# Antenna.net
KiCad netlist of a schematic drawn in Altium Designer
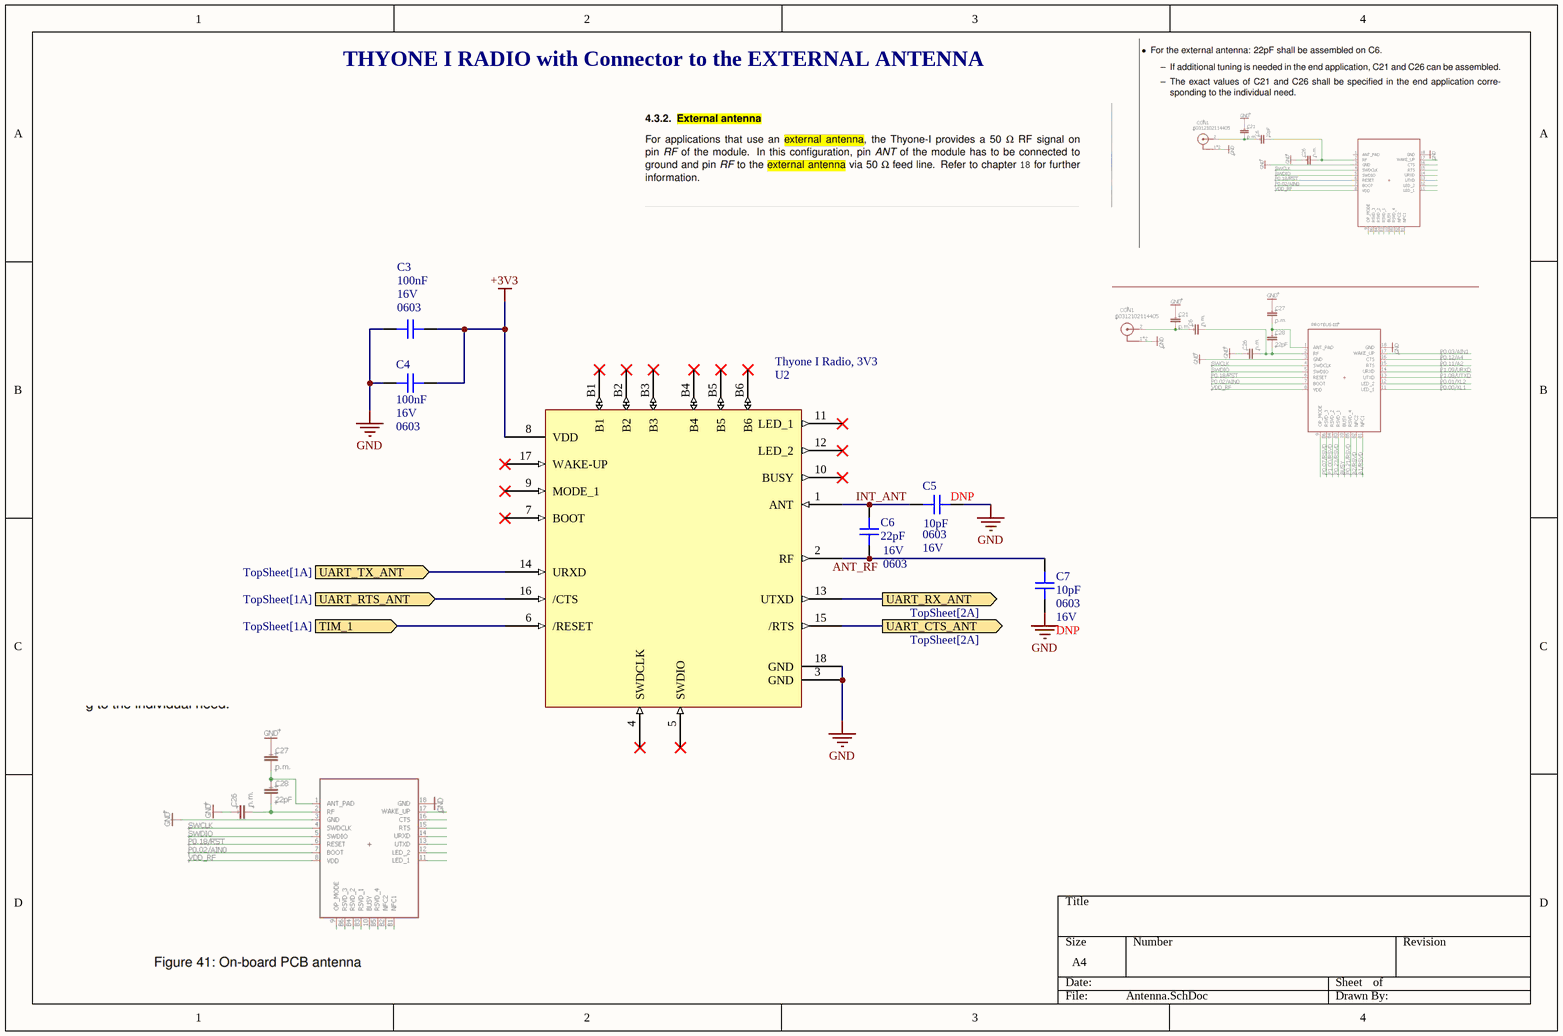
[diagram p0: Antenna.SchDoc]

(export (version "E")
  (design (tool "Eeschema 10.0.6"))
  (components
    (comp (ref "C3")
      (value "100nF")
      (footprint "0603_C")
      (description "CAP CER 0.1UF 16V X7R 0603")
      (fields
        (field (name "VOLTAGE - RATED") "16V")
        (field (name "TOLERANCE") "10%")
        (field (name "PACKAGE / CASE") "0603")
        (field (name "MANUFACTURE PART NUMBER") "KGM15AR71C104KM")
      )
      (libsource (lib "Aleksandra Popova") (part "Capacitor - Non Polarized"))
    )
    (comp (ref "C4")
      (value "100nF")
      (footprint "0603_C")
      (description "CAP CER 0.1UF 16V X7R 0603")
      (fields
        (field (name "VOLTAGE - RATED") "16V")
        (field (name "TOLERANCE") "10%")
        (field (name "PACKAGE / CASE") "0603")
        (field (name "MANUFACTURE PART NUMBER") "KGM15AR71C104KM")
      )
      (libsource (lib "Aleksandra Popova") (part "Capacitor - Non Polarized"))
    )
    (comp (ref "C5")
      (value "DNP")
      (footprint "0603_C")
      (description "CAP CER 10PF 16V C0G/NP0 0603")
      (fields
        (field (name "TOLERANCE") "5%")
        (field (name "MANUFACTURE PART NUMBER") "KGM15ACG1C100JT")
        (field (name "ALTIUM_VALUE") "10pF")
        (field (name "PACKAGE / CASE") "0603")
        (field (name "VOLTAGE - RATED") "16V")
      )
      (libsource (lib "Aleksandra Popova") (part "Capacitor - Non Polarized"))
    )
    (comp (ref "C6")
      (value "22pF")
      (footprint "0603_C")
      (description "CAP CER 22PF 16V C0G/NP0 0603")
      (fields
        (field (name "VOLTAGE - RATED") "16V")
        (field (name "TOLERANCE") "10%")
        (field (name "PACKAGE / CASE") "0603")
        (field (name "MANUFACTURE PART NUMBER") "KGM15ACG1C220KT")
      )
      (libsource (lib "Aleksandra Popova") (part "Capacitor - Non Polarized"))
    )
    (comp (ref "C7")
      (value "DNP")
      (footprint "0603_C")
      (description "CAP CER 10PF 16V C0G/NP0 0603")
      (fields
        (field (name "TOLERANCE") "5%")
        (field (name "MANUFACTURE PART NUMBER") "KGM15ACG1C100JT")
        (field (name "ALTIUM_VALUE") "10pF")
        (field (name "PACKAGE / CASE") "0603")
        (field (name "VOLTAGE - RATED") "16V")
      )
      (libsource (lib "Aleksandra Popova") (part "Capacitor - Non Polarized"))
    )
    (comp (ref "U2")
      (value "Thyone I Radio, 3V3")
      (footprint "WE-FP-4+")
      (libsource (lib "Schlib1") (part "2611011021000"))
    )
  )
  (nets
    (net (code "1") (name "+3V3") (class "Default")
      (node (ref "C3") (pin "2") (pinfunction "2_2") (pintype "passive"))
      (node (ref "C4") (pin "1") (pinfunction "1_1") (pintype "passive"))
      (node (ref "U2") (pin "8") (pinfunction "VDD_8") (pintype "passive"))
    )
    (net (code "2") (name "/ANT_RF") (class "Default")
      (node (ref "C6") (pin "1") (pinfunction "1_1") (pintype "passive"))
      (node (ref "C7") (pin "1") (pinfunction "1_1") (pintype "passive"))
      (node (ref "U2") (pin "2") (pinfunction "RF_2") (pintype "output"))
    )
    (net (code "3") (name "/INT_ANT") (class "Default")
      (node (ref "C5") (pin "2") (pinfunction "2_2") (pintype "passive"))
      (node (ref "C6") (pin "2") (pinfunction "2_2") (pintype "passive"))
      (node (ref "U2") (pin "1") (pinfunction "ANT_1") (pintype "input"))
    )
    (net (code "4") (name "/TIM_1") (class "Default")
      (node (ref "U2") (pin "6") (pinfunction "/RESET_6") (pintype "input"))
    )
    (net (code "5") (name "/UART_CTS_ANT") (class "Default")
      (node (ref "U2") (pin "15") (pinfunction "/RTS_15") (pintype "output"))
    )
    (net (code "6") (name "/UART_RTS_ANT") (class "Default")
      (node (ref "U2") (pin "16") (pinfunction "/CTS_16") (pintype "input"))
    )
    (net (code "7") (name "/UART_RX_ANT") (class "Default")
      (node (ref "U2") (pin "13") (pinfunction "UTXD_13") (pintype "output"))
    )
    (net (code "8") (name "/UART_TX_ANT") (class "Default")
      (node (ref "U2") (pin "14") (pinfunction "URXD_14") (pintype "input"))
    )
    (net (code "9") (name "GND") (class "Default")
      (node (ref "C3") (pin "1") (pinfunction "1_1") (pintype "passive"))
      (node (ref "C4") (pin "2") (pinfunction "2_2") (pintype "passive"))
      (node (ref "C5") (pin "1") (pinfunction "1_1") (pintype "passive"))
      (node (ref "C7") (pin "2") (pinfunction "2_2") (pintype "passive"))
      (node (ref "U2") (pin "18") (pinfunction "GND_18") (pintype "passive"))
      (node (ref "U2") (pin "3") (pinfunction "GND_3") (pintype "passive"))
    )
    (net (code "10") (name "unconnected-(U2-BOOT-Pad7)") (class "Default")
      (node (ref "U2") (pin "7") (pinfunction "BOOT_7") (pintype "input+no_connect"))
    )
    (net (code "11") (name "unconnected-(U2-BUSY-Pad10)") (class "Default")
      (node (ref "U2") (pin "10") (pinfunction "BUSY_10") (pintype "output+no_connect"))
    )
    (net (code "12") (name "unconnected-(U2-LED_1-Pad11)") (class "Default")
      (node (ref "U2") (pin "11") (pinfunction "LED_1_11") (pintype "output+no_connect"))
    )
    (net (code "13") (name "unconnected-(U2-LED_2-Pad12)") (class "Default")
      (node (ref "U2") (pin "12") (pinfunction "LED_2_12") (pintype "output+no_connect"))
    )
    (net (code "14") (name "unconnected-(U2-MODE_1-Pad9)") (class "Default")
      (node (ref "U2") (pin "9") (pinfunction "MODE_1_9") (pintype "input+no_connect"))
    )
    (net (code "15") (name "unconnected-(U2-PadB1)") (class "Default")
      (node (ref "U2") (pin "B1") (pinfunction "B1_B1") (pintype "bidirectional+no_connect"))
    )
    (net (code "16") (name "unconnected-(U2-PadB2)") (class "Default")
      (node (ref "U2") (pin "B2") (pinfunction "B2_B2") (pintype "bidirectional+no_connect"))
    )
    (net (code "17") (name "unconnected-(U2-PadB3)") (class "Default")
      (node (ref "U2") (pin "B3") (pinfunction "B3_B3") (pintype "bidirectional+no_connect"))
    )
    (net (code "18") (name "unconnected-(U2-PadB4)") (class "Default")
      (node (ref "U2") (pin "B4") (pinfunction "B4_B4") (pintype "bidirectional+no_connect"))
    )
    (net (code "19") (name "unconnected-(U2-PadB5)") (class "Default")
      (node (ref "U2") (pin "B5") (pinfunction "B5_B5") (pintype "bidirectional+no_connect"))
    )
    (net (code "20") (name "unconnected-(U2-PadB6)") (class "Default")
      (node (ref "U2") (pin "B6") (pinfunction "B6_B6") (pintype "bidirectional+no_connect"))
    )
    (net (code "21") (name "unconnected-(U2-SWDCLK-Pad4)") (class "Default")
      (node (ref "U2") (pin "4") (pinfunction "SWDCLK_4") (pintype "input+no_connect"))
    )
    (net (code "22") (name "unconnected-(U2-SWDIO-Pad5)") (class "Default")
      (node (ref "U2") (pin "5") (pinfunction "SWDIO_5") (pintype "input+no_connect"))
    )
    (net (code "23") (name "unconnected-(U2-WAKE-UP-Pad17)") (class "Default")
      (node (ref "U2") (pin "17") (pinfunction "WAKE-UP_17") (pintype "input+no_connect"))
    )
  )
)
